# bridge.net
KiCad netlist of a schematic drawn in Altium Designer
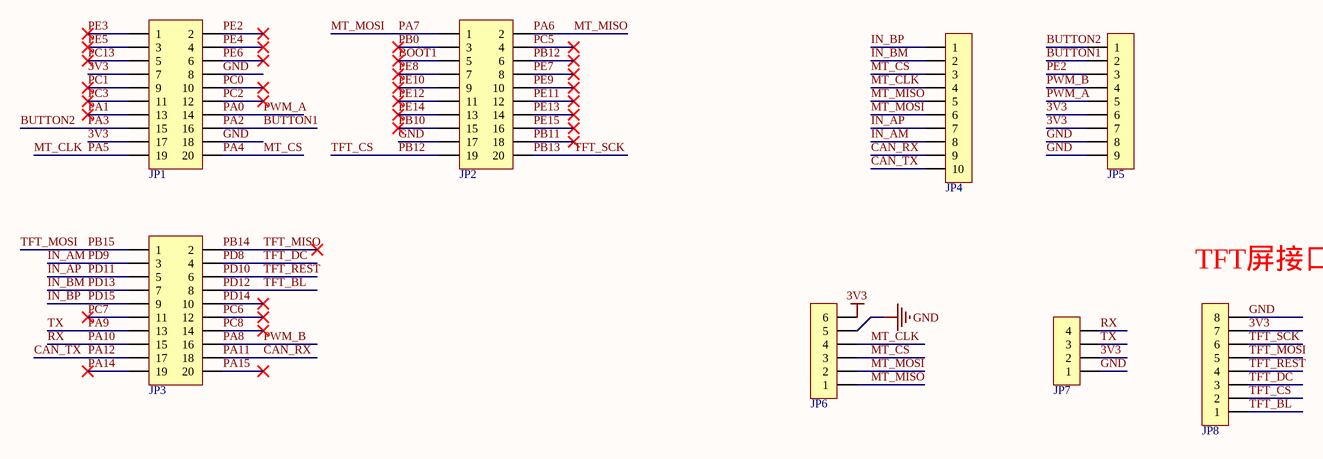
[diagram p0: bridge.SchDoc]

(export (version "E")
  (design (tool "Eeschema 10.0.6"))
  (components
    (comp (ref "JP1")
      (value "Header 2X10")
      (footprint "HDR2.54-LI-2x10P")
      (description "10*2P接插件")
      (libsource (lib "5.5 - 2.54mm连接器(KF2EDGK_XH2.54_2.54排针排母)") (part "Header 10X2"))
    )
    (comp (ref "JP2")
      (value "Header 2X10")
      (footprint "HDR2.54-LI-2x10P")
      (description "10*2P接插件")
      (libsource (lib "5.5 - 2.54mm连接器(KF2EDGK_XH2.54_2.54排针排母)") (part "Header 10X2"))
    )
    (comp (ref "JP3")
      (value "Header 2X10")
      (footprint "HDR2.54-LI-2x10P")
      (description "10*2P接插件")
      (libsource (lib "5.5 - 2.54mm连接器(KF2EDGK_XH2.54_2.54排针排母)") (part "Header 10X2"))
    )
    (comp (ref "JP4")
      (value "CON-10P")
      (footprint "SH1.0-WT-10P")
      (description "10P连接器")
      (libsource (lib "5.0 - 1.00mm连接器(FPC1.0_SH1.0_1.0排针排母)") (part "Header 10"))
    )
    (comp (ref "JP5")
      (value "CON-9P")
      (footprint "SH1.0-WT-9P")
      (description "9P连接器")
      (libsource (lib "5.0 - 1.00mm连接器(FPC1.0_SH1.0_1.0排针排母)") (part "Header 9"))
    )
    (comp (ref "JP6")
      (value "HDR-1X6")
      (footprint "HDR2.54-LI-6P")
      (description "6P接插件")
      (libsource (lib "5.5 - 2.54mm连接器(KF2EDGK_XH2.54_2.54排针排母)") (part "Header 6"))
    )
    (comp (ref "JP7")
      (value "HDR-1X4")
      (footprint "HDR2.54-LI-4P")
      (description "4P接插件")
      (libsource (lib "5.5 - 2.54mm连接器(KF2EDGK_XH2.54_2.54排针排母)") (part "Header 4"))
    )
    (comp (ref "JP8")
      (value "HDR-1X8")
      (footprint "HDR2.54-M-LI-8P")
      (description "8P接插件")
      (libsource (lib "5.5 - 2.54mm连接器(KF2EDGK_XH2.54_2.54排针排母)") (part "Header 8"))
    )
  )
  (nets
    (net (code "1") (name "/BOOT1") (class "Default")
      (node (ref "JP2") (pin "5") (pinfunction "5_5") (pintype "passive+no_connect"))
    )
    (net (code "2") (name "/BUTTON1") (class "Default")
      (node (ref "JP1") (pin "16") (pinfunction "16_16") (pintype "passive"))
      (node (ref "JP5") (pin "2") (pinfunction "2_2") (pintype "passive"))
    )
    (net (code "3") (name "/BUTTON2") (class "Default")
      (node (ref "JP1") (pin "15") (pinfunction "15_15") (pintype "passive"))
      (node (ref "JP5") (pin "1") (pinfunction "1_1") (pintype "passive"))
    )
    (net (code "4") (name "/CAN_RX") (class "Default")
      (node (ref "JP3") (pin "18") (pinfunction "18_18") (pintype "passive"))
      (node (ref "JP4") (pin "9") (pinfunction "9_9") (pintype "passive"))
    )
    (net (code "5") (name "/CAN_TX") (class "Default")
      (node (ref "JP3") (pin "17") (pinfunction "17_17") (pintype "passive"))
      (node (ref "JP4") (pin "10") (pinfunction "10_10") (pintype "passive"))
    )
    (net (code "6") (name "/IN_AM") (class "Default")
      (node (ref "JP3") (pin "3") (pinfunction "3_3") (pintype "passive"))
      (node (ref "JP4") (pin "8") (pinfunction "8_8") (pintype "passive"))
    )
    (net (code "7") (name "/IN_AP") (class "Default")
      (node (ref "JP3") (pin "5") (pinfunction "5_5") (pintype "passive"))
      (node (ref "JP4") (pin "7") (pinfunction "7_7") (pintype "passive"))
    )
    (net (code "8") (name "/IN_BM") (class "Default")
      (node (ref "JP3") (pin "7") (pinfunction "7_7") (pintype "passive"))
      (node (ref "JP4") (pin "2") (pinfunction "2_2") (pintype "passive"))
    )
    (net (code "9") (name "/IN_BP") (class "Default")
      (node (ref "JP3") (pin "9") (pinfunction "9_9") (pintype "passive"))
      (node (ref "JP4") (pin "1") (pinfunction "1_1") (pintype "passive"))
    )
    (net (code "10") (name "/MT_CLK") (class "Default")
      (node (ref "JP1") (pin "19") (pinfunction "19_19") (pintype "passive"))
      (node (ref "JP4") (pin "4") (pinfunction "4_4") (pintype "passive"))
      (node (ref "JP6") (pin "4") (pinfunction "4_4") (pintype "passive"))
    )
    (net (code "11") (name "/MT_CS") (class "Default")
      (node (ref "JP1") (pin "20") (pinfunction "20_20") (pintype "passive"))
      (node (ref "JP4") (pin "3") (pinfunction "3_3") (pintype "passive"))
      (node (ref "JP6") (pin "3") (pinfunction "3_3") (pintype "passive"))
    )
    (net (code "12") (name "/MT_MISO") (class "Default")
      (node (ref "JP2") (pin "2") (pinfunction "2_2") (pintype "passive"))
      (node (ref "JP4") (pin "5") (pinfunction "5_5") (pintype "passive"))
      (node (ref "JP6") (pin "1") (pinfunction "1_1") (pintype "passive"))
    )
    (net (code "13") (name "/MT_MOSI") (class "Default")
      (node (ref "JP2") (pin "1") (pinfunction "1_1") (pintype "passive"))
      (node (ref "JP4") (pin "6") (pinfunction "6_6") (pintype "passive"))
      (node (ref "JP6") (pin "2") (pinfunction "2_2") (pintype "passive"))
    )
    (net (code "14") (name "/PA0") (class "Default")
      (node (ref "JP1") (pin "14") (pinfunction "14_14") (pintype "passive"))
      (node (ref "JP5") (pin "5") (pinfunction "5_5") (pintype "passive"))
    )
    (net (code "15") (name "/PA1") (class "Default")
      (node (ref "JP1") (pin "13") (pinfunction "13_13") (pintype "passive+no_connect"))
    )
    (net (code "16") (name "/PA8") (class "Default")
      (node (ref "JP3") (pin "16") (pinfunction "16_16") (pintype "passive"))
      (node (ref "JP5") (pin "4") (pinfunction "4_4") (pintype "passive"))
    )
    (net (code "17") (name "/PA9") (class "Default")
      (node (ref "JP3") (pin "13") (pinfunction "13_13") (pintype "passive"))
      (node (ref "JP7") (pin "3") (pinfunction "3_3") (pintype "passive"))
    )
    (net (code "18") (name "/PA10") (class "Default")
      (node (ref "JP3") (pin "15") (pinfunction "15_15") (pintype "passive"))
      (node (ref "JP7") (pin "4") (pinfunction "4_4") (pintype "passive"))
    )
    (net (code "19") (name "/PA14") (class "Default")
      (node (ref "JP3") (pin "19") (pinfunction "19_19") (pintype "passive+no_connect"))
    )
    (net (code "20") (name "/PA15") (class "Default")
      (node (ref "JP3") (pin "20") (pinfunction "20_20") (pintype "passive+no_connect"))
    )
    (net (code "21") (name "/PB0") (class "Default")
      (node (ref "JP2") (pin "3") (pinfunction "3_3") (pintype "passive+no_connect"))
    )
    (net (code "22") (name "/PB10") (class "Default")
      (node (ref "JP2") (pin "15") (pinfunction "15_15") (pintype "passive+no_connect"))
    )
    (net (code "23") (name "/PB11") (class "Default")
      (node (ref "JP2") (pin "18") (pinfunction "18_18") (pintype "passive+no_connect"))
    )
    (net (code "24") (name "/PB12") (class "Default")
      (node (ref "JP2") (pin "19") (pinfunction "19_19") (pintype "passive"))
      (node (ref "JP2") (pin "6") (pinfunction "6_6") (pintype "passive"))
      (node (ref "JP8") (pin "2") (pinfunction "2_2") (pintype "passive"))
    )
    (net (code "25") (name "/PB13") (class "Default")
      (node (ref "JP2") (pin "20") (pinfunction "20_20") (pintype "passive"))
      (node (ref "JP8") (pin "6") (pinfunction "6_6") (pintype "passive"))
    )
    (net (code "26") (name "/PB14") (class "Default")
      (node (ref "JP3") (pin "2") (pinfunction "2_2") (pintype "passive+no_connect"))
    )
    (net (code "27") (name "/PB15") (class "Default")
      (node (ref "JP3") (pin "1") (pinfunction "1_1") (pintype "passive"))
      (node (ref "JP8") (pin "5") (pinfunction "5_5") (pintype "passive"))
    )
    (net (code "28") (name "/PC0") (class "Default")
      (node (ref "JP1") (pin "10") (pinfunction "10_10") (pintype "passive+no_connect"))
    )
    (net (code "29") (name "/PC1") (class "Default")
      (node (ref "JP1") (pin "9") (pinfunction "9_9") (pintype "passive+no_connect"))
    )
    (net (code "30") (name "/PC2") (class "Default")
      (node (ref "JP1") (pin "12") (pinfunction "12_12") (pintype "passive+no_connect"))
    )
    (net (code "31") (name "/PC3") (class "Default")
      (node (ref "JP1") (pin "11") (pinfunction "11_11") (pintype "passive+no_connect"))
    )
    (net (code "32") (name "/PC5") (class "Default")
      (node (ref "JP2") (pin "4") (pinfunction "4_4") (pintype "passive+no_connect"))
    )
    (net (code "33") (name "/PC6") (class "Default")
      (node (ref "JP3") (pin "12") (pinfunction "12_12") (pintype "passive+no_connect"))
    )
    (net (code "34") (name "/PC7") (class "Default")
      (node (ref "JP3") (pin "11") (pinfunction "11_11") (pintype "passive+no_connect"))
    )
    (net (code "35") (name "/PC8") (class "Default")
      (node (ref "JP3") (pin "14") (pinfunction "14_14") (pintype "passive+no_connect"))
    )
    (net (code "36") (name "/PC13") (class "Default")
      (node (ref "JP1") (pin "5") (pinfunction "5_5") (pintype "passive+no_connect"))
    )
    (net (code "37") (name "/PD8") (class "Default")
      (node (ref "JP3") (pin "4") (pinfunction "4_4") (pintype "passive"))
      (node (ref "JP8") (pin "3") (pinfunction "3_3") (pintype "passive"))
    )
    (net (code "38") (name "/PD10") (class "Default")
      (node (ref "JP3") (pin "6") (pinfunction "6_6") (pintype "passive"))
      (node (ref "JP8") (pin "4") (pinfunction "4_4") (pintype "passive"))
    )
    (net (code "39") (name "/PD12") (class "Default")
      (node (ref "JP3") (pin "8") (pinfunction "8_8") (pintype "passive"))
      (node (ref "JP8") (pin "1") (pinfunction "1_1") (pintype "passive"))
    )
    (net (code "40") (name "/PD14") (class "Default")
      (node (ref "JP3") (pin "10") (pinfunction "10_10") (pintype "passive+no_connect"))
    )
    (net (code "41") (name "/PE2") (class "Default")
      (node (ref "JP1") (pin "2") (pinfunction "2_2") (pintype "passive"))
      (node (ref "JP5") (pin "3") (pinfunction "3_3") (pintype "passive"))
    )
    (net (code "42") (name "/PE3") (class "Default")
      (node (ref "JP1") (pin "1") (pinfunction "1_1") (pintype "passive+no_connect"))
    )
    (net (code "43") (name "/PE4") (class "Default")
      (node (ref "JP1") (pin "4") (pinfunction "4_4") (pintype "passive+no_connect"))
    )
    (net (code "44") (name "/PE5") (class "Default")
      (node (ref "JP1") (pin "3") (pinfunction "3_3") (pintype "passive+no_connect"))
    )
    (net (code "45") (name "/PE6") (class "Default")
      (node (ref "JP1") (pin "6") (pinfunction "6_6") (pintype "passive+no_connect"))
    )
    (net (code "46") (name "/PE7") (class "Default")
      (node (ref "JP2") (pin "8") (pinfunction "8_8") (pintype "passive+no_connect"))
    )
    (net (code "47") (name "/PE8") (class "Default")
      (node (ref "JP2") (pin "7") (pinfunction "7_7") (pintype "passive+no_connect"))
    )
    (net (code "48") (name "/PE9") (class "Default")
      (node (ref "JP2") (pin "10") (pinfunction "10_10") (pintype "passive+no_connect"))
    )
    (net (code "49") (name "/PE10") (class "Default")
      (node (ref "JP2") (pin "9") (pinfunction "9_9") (pintype "passive+no_connect"))
    )
    (net (code "50") (name "/PE11") (class "Default")
      (node (ref "JP2") (pin "12") (pinfunction "12_12") (pintype "passive+no_connect"))
    )
    (net (code "51") (name "/PE12") (class "Default")
      (node (ref "JP2") (pin "11") (pinfunction "11_11") (pintype "passive+no_connect"))
    )
    (net (code "52") (name "/PE13") (class "Default")
      (node (ref "JP2") (pin "14") (pinfunction "14_14") (pintype "passive+no_connect"))
    )
    (net (code "53") (name "/PE14") (class "Default")
      (node (ref "JP2") (pin "13") (pinfunction "13_13") (pintype "passive+no_connect"))
    )
    (net (code "54") (name "/PE15") (class "Default")
      (node (ref "JP2") (pin "16") (pinfunction "16_16") (pintype "passive+no_connect"))
    )
    (net (code "55") (name "3V3") (class "Default")
      (node (ref "JP1") (pin "17") (pinfunction "17_17") (pintype "passive"))
      (node (ref "JP1") (pin "7") (pinfunction "7_7") (pintype "passive"))
      (node (ref "JP5") (pin "6") (pinfunction "6_6") (pintype "passive"))
      (node (ref "JP5") (pin "7") (pinfunction "7_7") (pintype "passive"))
      (node (ref "JP6") (pin "6") (pinfunction "6_6") (pintype "passive"))
      (node (ref "JP7") (pin "2") (pinfunction "2_2") (pintype "passive"))
      (node (ref "JP8") (pin "7") (pinfunction "7_7") (pintype "passive"))
    )
    (net (code "56") (name "GND") (class "Default")
      (node (ref "JP1") (pin "18") (pinfunction "18_18") (pintype "passive"))
      (node (ref "JP1") (pin "8") (pinfunction "8_8") (pintype "passive"))
      (node (ref "JP2") (pin "17") (pinfunction "17_17") (pintype "passive"))
      (node (ref "JP5") (pin "8") (pinfunction "8_8") (pintype "passive"))
      (node (ref "JP5") (pin "9") (pinfunction "9_9") (pintype "passive"))
      (node (ref "JP6") (pin "5") (pinfunction "5_5") (pintype "passive"))
      (node (ref "JP7") (pin "1") (pinfunction "1_1") (pintype "passive"))
      (node (ref "JP8") (pin "8") (pinfunction "8_8") (pintype "passive"))
    )
  )
)
